# ETH_10M100M_RMII_LAN8742.net
KiCad netlist of a schematic drawn in Altium Designer
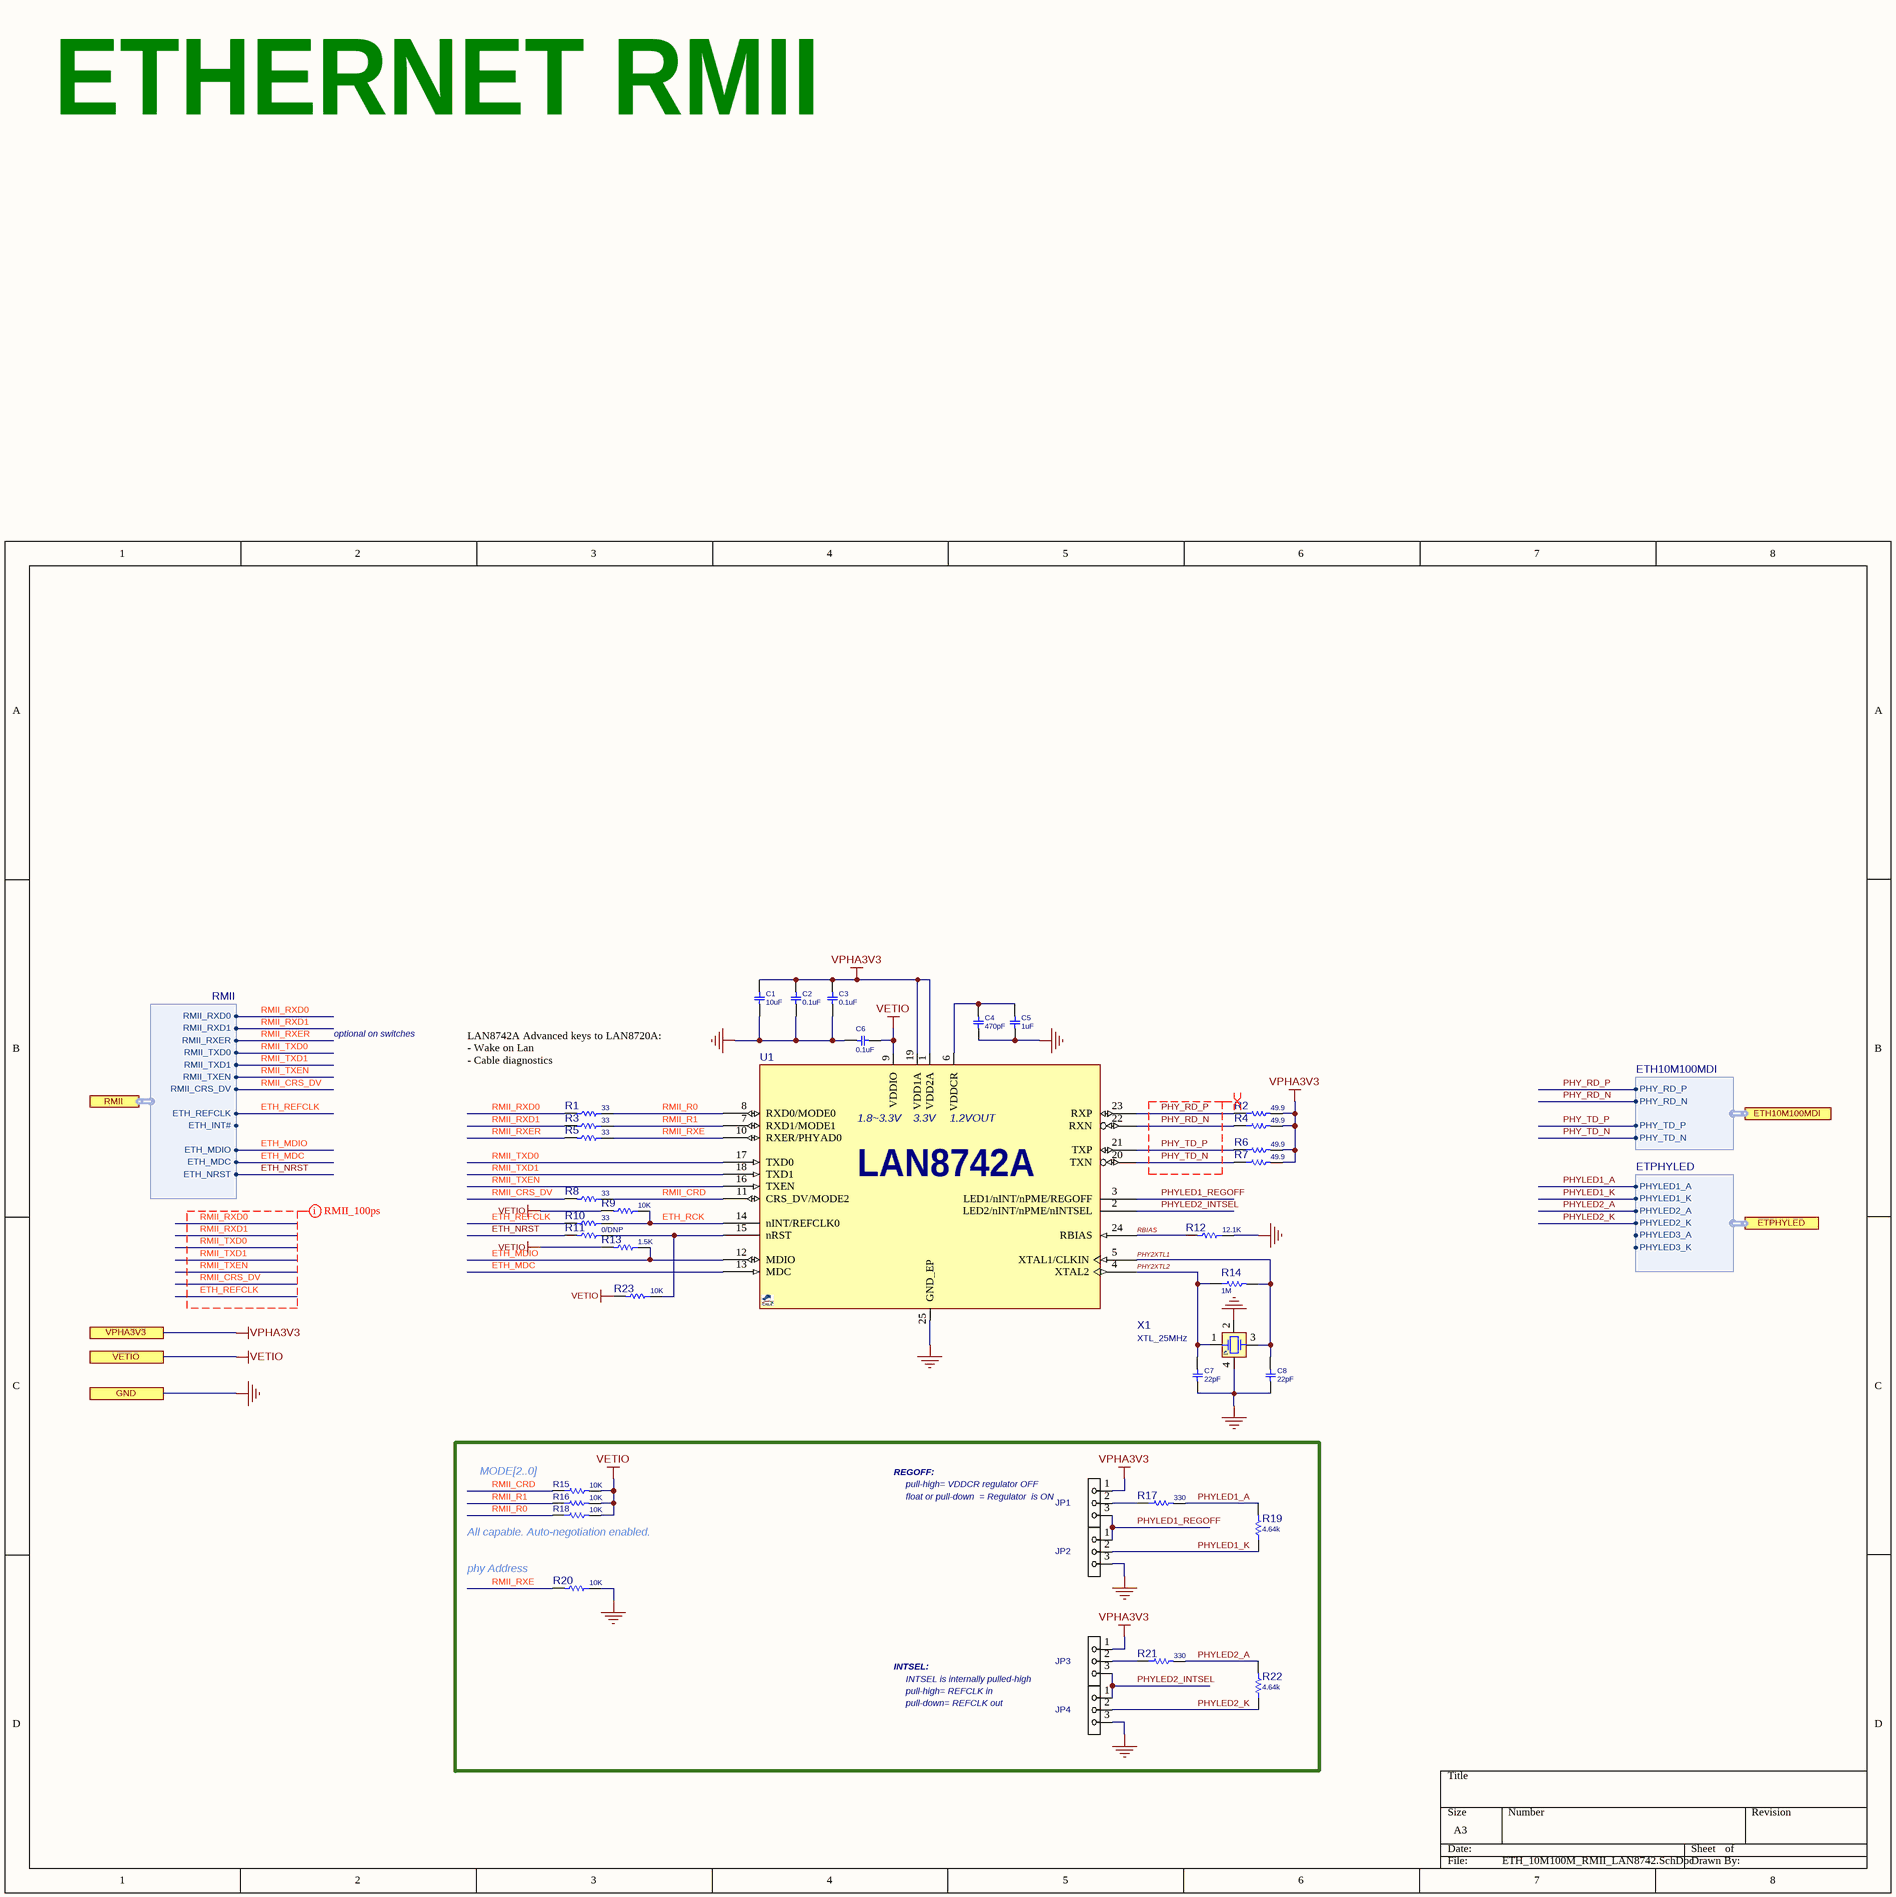
[diagram p0: ETH_10M100M_RMII_LAN8742.SchDoc]

(export (version "E")
  (design (tool "Eeschema 10.0.6"))
  (components
    (comp (ref "C1")
      (value "10uF")
      (footprint "C0402")
      (description "CAP, MLCC")
      (libsource (lib "mlcc_smd_passive") (part "CAP_SMD_MLCC_100n50TDK"))
    )
    (comp (ref "C2")
      (value "0.1uF")
      (footprint "C0402")
      (description "CAP, MLCC")
      (libsource (lib "mlcc_smd_passive") (part "CAP_SMD_MLCC_100n50TDK"))
    )
    (comp (ref "C3")
      (value "0.1uF")
      (footprint "C0402")
      (description "CAP, MLCC")
      (libsource (lib "mlcc_smd_passive") (part "CAP_SMD_MLCC_100n50TDK"))
    )
    (comp (ref "C4")
      (value "470pF")
      (footprint "C0402")
      (description "CAP, MLCC")
      (libsource (lib "mlcc_smd_passive") (part "CAP_SMD_MLCC_100n50TDK"))
    )
    (comp (ref "C5")
      (value "1uF")
      (footprint "C0402")
      (description "CAP, MLCC")
      (libsource (lib "mlcc_smd_passive") (part "CAP_SMD_MLCC_100n50TDK"))
    )
    (comp (ref "C6")
      (value "0.1uF")
      (footprint "C0402")
      (description "CAP, MLCC")
      (libsource (lib "mlcc_smd_passive") (part "CAP_SMD_MLCC_100n50TDK"))
    )
    (comp (ref "C7")
      (value "22pF")
      (footprint "C0402")
      (description "CAP, MLCC")
      (libsource (lib "mlcc_smd_passive") (part "CAP_SMD_MLCC_100n50TDK"))
    )
    (comp (ref "C8")
      (value "22pF")
      (footprint "C0402")
      (description "CAP, MLCC")
      (libsource (lib "mlcc_smd_passive") (part "CAP_SMD_MLCC_100n50TDK"))
    )
    (comp (ref "JP1")
      (value "JMPHDR3PIN")
      (footprint "JP_3_60W")
      (description "JUMPER, HEADER 3PIN")
      (fields (field (name "MANF") "MANF") (field (name "MANF_P#") "MANF_P#"))
      (libsource (lib "test-tp_jumper") (part "JUMPER_SOLDER_3P"))
    )
    (comp (ref "JP2")
      (value "JMPHDR3PIN")
      (footprint "JP_3_60W")
      (description "JUMPER, HEADER 3PIN")
      (fields (field (name "MANF") "MANF") (field (name "MANF_P#") "MANF_P#"))
      (libsource (lib "test-tp_jumper") (part "JUMPER_SOLDER_3P"))
    )
    (comp (ref "JP3")
      (value "JMPHDR3PIN")
      (footprint "JP_3_60W")
      (description "JUMPER, HEADER 3PIN")
      (fields (field (name "MANF") "MANF") (field (name "MANF_P#") "MANF_P#"))
      (libsource (lib "test-tp_jumper") (part "JUMPER_SOLDER_3P"))
    )
    (comp (ref "JP4")
      (value "JMPHDR3PIN")
      (footprint "JP_3_60W")
      (description "JUMPER, HEADER 3PIN")
      (fields (field (name "MANF") "MANF") (field (name "MANF_P#") "MANF_P#"))
      (libsource (lib "test-tp_jumper") (part "JUMPER_SOLDER_3P"))
    )
    (comp (ref "R1")
      (value "33")
      (footprint "R0402")
      (description "RESISTOR, SMD, THICK FILM, YAGEO")
      (fields (field (name "MANF_P#") "RC0402FR-071KL") (field (name "MANF") "Yageo"))
      (libsource (lib "res_smd_Yageo0402_thickfilm") (part "RES_SMD_1K_0402YK"))
    )
    (comp (ref "R2")
      (value "49.9")
      (footprint "R0402")
      (description "RESISTOR, SMD, THICK FILM, YAGEO")
      (fields (field (name "MANF_P#") "RC0402FR-071KL") (field (name "MANF") "Yageo"))
      (libsource (lib "res_smd_Yageo0402_thickfilm") (part "RES_SMD_1K_0402YK"))
    )
    (comp (ref "R3")
      (value "33")
      (footprint "R0402")
      (description "RESISTOR, SMD, THICK FILM, YAGEO")
      (fields (field (name "MANF_P#") "RC0402FR-071KL") (field (name "MANF") "Yageo"))
      (libsource (lib "res_smd_Yageo0402_thickfilm") (part "RES_SMD_1K_0402YK"))
    )
    (comp (ref "R4")
      (value "49.9")
      (footprint "R0402")
      (description "RESISTOR, SMD, THICK FILM, YAGEO")
      (fields (field (name "MANF_P#") "RC0402FR-071KL") (field (name "MANF") "Yageo"))
      (libsource (lib "res_smd_Yageo0402_thickfilm") (part "RES_SMD_1K_0402YK"))
    )
    (comp (ref "R5")
      (value "33")
      (footprint "R0402")
      (description "RESISTOR, SMD, THICK FILM, YAGEO")
      (fields (field (name "MANF_P#") "RC0402FR-071KL") (field (name "MANF") "Yageo"))
      (libsource (lib "res_smd_Yageo0402_thickfilm") (part "RES_SMD_1K_0402YK"))
    )
    (comp (ref "R6")
      (value "49.9")
      (footprint "R0402")
      (description "RESISTOR, SMD, THICK FILM, YAGEO")
      (fields (field (name "MANF_P#") "RC0402FR-071KL") (field (name "MANF") "Yageo"))
      (libsource (lib "res_smd_Yageo0402_thickfilm") (part "RES_SMD_1K_0402YK"))
    )
    (comp (ref "R7")
      (value "49.9")
      (footprint "R0402")
      (description "RESISTOR, SMD, THICK FILM, YAGEO")
      (fields (field (name "MANF_P#") "RC0402FR-071KL") (field (name "MANF") "Yageo"))
      (libsource (lib "res_smd_Yageo0402_thickfilm") (part "RES_SMD_1K_0402YK"))
    )
    (comp (ref "R8")
      (value "33")
      (footprint "R0402")
      (description "RESISTOR, SMD, THICK FILM, YAGEO")
      (fields (field (name "MANF_P#") "RC0402FR-071KL") (field (name "MANF") "Yageo"))
      (libsource (lib "res_smd_Yageo0402_thickfilm") (part "RES_SMD_1K_0402YK"))
    )
    (comp (ref "R9")
      (value "10K")
      (footprint "R0402")
      (description "RESISTOR, SMD, THICK FILM, YAGEO")
      (fields (field (name "MANF_P#") "RC0402FR-071KL") (field (name "MANF") "Yageo"))
      (libsource (lib "res_smd_Yageo0402_thickfilm") (part "RES_SMD_1K_0402YK"))
    )
    (comp (ref "R10")
      (value "33")
      (footprint "R0402")
      (description "RESISTOR, SMD, THICK FILM, YAGEO")
      (fields (field (name "MANF_P#") "RC0402FR-071KL") (field (name "MANF") "Yageo"))
      (libsource (lib "res_smd_Yageo0402_thickfilm") (part "RES_SMD_1K_0402YK"))
    )
    (comp (ref "R11")
      (value "0/DNP")
      (footprint "R0402")
      (description "RESISTOR, SMD, THICK FILM, YAGEO")
      (fields (field (name "MANF_P#") "RC0402FR-071KL") (field (name "MANF") "Yageo"))
      (libsource (lib "res_smd_Yageo0402_thickfilm") (part "RES_SMD_1K_0402YK"))
    )
    (comp (ref "R12")
      (value "12.1K")
      (footprint "R0402")
      (description "RESISTOR, SMD, THICK FILM, YAGEO")
      (fields (field (name "MANF_P#") "RC0402FR-071KL") (field (name "MANF") "Yageo"))
      (libsource (lib "res_smd_Yageo0402_thickfilm") (part "RES_SMD_1K_0402YK"))
    )
    (comp (ref "R13")
      (value "1.5K")
      (footprint "R0402")
      (description "RESISTOR, SMD, THICK FILM, YAGEO")
      (fields (field (name "MANF_P#") "RC0402FR-071KL") (field (name "MANF") "Yageo"))
      (libsource (lib "res_smd_Yageo0402_thickfilm") (part "RES_SMD_1K_0402YK"))
    )
    (comp (ref "R14")
      (value "1M")
      (footprint "R0402")
      (description "RESISTOR, SMD")
      (fields (field (name "MANF") "Yageo") (field (name "MANF_P#") "RC0402FR-071ML"))
      (libsource (lib "res_smd_KoaSpeer0402") (part "RES_SMD_10K_0402"))
    )
    (comp (ref "R15")
      (value "10K")
      (footprint "R0402")
      (description "RESISTOR, SMD, THICK FILM, YAGEO")
      (fields (field (name "MANF_P#") "RC0402FR-071KL") (field (name "MANF") "Yageo"))
      (libsource (lib "res_smd_Yageo0402_thickfilm") (part "RES_SMD_1K_0402YK"))
    )
    (comp (ref "R16")
      (value "10K")
      (footprint "R0402")
      (description "RESISTOR, SMD, THICK FILM, YAGEO")
      (fields (field (name "MANF_P#") "RC0402FR-071KL") (field (name "MANF") "Yageo"))
      (libsource (lib "res_smd_Yageo0402_thickfilm") (part "RES_SMD_1K_0402YK"))
    )
    (comp (ref "R17")
      (value "330")
      (footprint "R0402")
      (description "RESISTOR, SMD, THICK FILM, YAGEO")
      (fields (field (name "MANF_P#") "RC0402FR-071KL") (field (name "MANF") "Yageo"))
      (libsource (lib "res_smd_Yageo0402_thickfilm") (part "RES_SMD_1K_0402YK"))
    )
    (comp (ref "R18")
      (value "10K")
      (footprint "R0402")
      (description "RESISTOR, SMD, THICK FILM, YAGEO")
      (fields (field (name "MANF_P#") "RC0402FR-071KL") (field (name "MANF") "Yageo"))
      (libsource (lib "res_smd_Yageo0402_thickfilm") (part "RES_SMD_1K_0402YK"))
    )
    (comp (ref "R19")
      (value "4.64k")
      (footprint "R0402")
      (description "RESISTOR, SMD, THICK FILM, YAGEO")
      (fields (field (name "MANF_P#") "RC0402FR-071KL") (field (name "MANF") "Yageo"))
      (libsource (lib "res_smd_Yageo0402_thickfilm") (part "RES_SMD_1K_0402YK"))
    )
    (comp (ref "R20")
      (value "10K")
      (footprint "R0402")
      (description "RESISTOR, SMD, THICK FILM, YAGEO")
      (fields (field (name "MANF_P#") "RC0402FR-071KL") (field (name "MANF") "Yageo"))
      (libsource (lib "res_smd_Yageo0402_thickfilm") (part "RES_SMD_1K_0402YK"))
    )
    (comp (ref "R21")
      (value "330")
      (footprint "R0402")
      (description "RESISTOR, SMD, THICK FILM, YAGEO")
      (fields (field (name "MANF_P#") "RC0402FR-071KL") (field (name "MANF") "Yageo"))
      (libsource (lib "res_smd_Yageo0402_thickfilm") (part "RES_SMD_1K_0402YK"))
    )
    (comp (ref "R22")
      (value "4.64k")
      (footprint "R0402")
      (description "RESISTOR, SMD, THICK FILM, YAGEO")
      (fields (field (name "MANF_P#") "RC0402FR-071KL") (field (name "MANF") "Yageo"))
      (libsource (lib "res_smd_Yageo0402_thickfilm") (part "RES_SMD_1K_0402YK"))
    )
    (comp (ref "R23")
      (value "10K")
      (footprint "R0402")
      (description "RESISTOR, SMD, THICK FILM, YAGEO")
      (fields (field (name "MANF_P#") "RC0402FR-071KL") (field (name "MANF") "Yageo"))
      (libsource (lib "res_smd_Yageo0402_thickfilm") (part "RES_SMD_1K_0402YK"))
    )
    (comp (ref "U1")
      (value "LAN8742A")
      (footprint "QFN50_24T")
      (description "Ethernet Transceiver, 10/100, RMII, 1.6-3.6V QFN24")
      (fields (field (name "MANF") "SMSC, MICROCHIP") (field (name "MANF_P#") "LAN8742AI-CZ"))
      (libsource (lib "ethernet") (part "LAN8742_QFN24"))
    )
    (comp (ref "X1")
      (value "XTL_25MHz")
      (footprint "XTL_4_3225")
      (description "CRYSTAL 25.00 MHZ 18pF, 10PPM")
      (fields (field (name "MANF") "EPSON") (field (name "MANF_P#") "TSX-3225 25.0000MF10P-C3"))
      (libsource (lib "crystal_osc") (part "XTL_4_25MHz_3225"))
    )
  )
  (nets
    (net (code "4") (name "/ETH_MDC") (class "Default")
      (node (ref "U1") (pin "13") (pinfunction "MDC_13") (pintype "input"))
    )
    (net (code "5") (name "/ETH_MDIO") (class "Default")
      (node (ref "R13") (pin "1") (pinfunction "1_1") (pintype "passive"))
      (node (ref "U1") (pin "12") (pinfunction "MDIO_12") (pintype "bidirectional"))
    )
    (net (code "6") (name "/ETH_NRST") (class "Default")
      (node (ref "R11") (pin "2") (pinfunction "2_2") (pintype "passive"))
    )
    (net (code "7") (name "/ETH_RCK") (class "Default")
      (node (ref "R10") (pin "1") (pinfunction "1_1") (pintype "passive"))
      (node (ref "R9") (pin "1") (pinfunction "1_1") (pintype "passive"))
      (node (ref "U1") (pin "14") (pinfunction "nINT/REFCLK0_14") (pintype "passive"))
    )
    (net (code "8") (name "/ETH_REFCLK") (class "Default")
      (node (ref "R10") (pin "2") (pinfunction "2_2") (pintype "passive"))
    )
    (net (code "9") (name "/PHY2XTL1") (class "Default")
      (node (ref "C8") (pin "1") (pinfunction "1_1") (pintype "passive"))
      (node (ref "R14") (pin "2") (pinfunction "2_2") (pintype "passive"))
      (node (ref "U1") (pin "5") (pinfunction "XTAL1/CLKIN_5") (pintype "input"))
      (node (ref "X1") (pin "3") (pinfunction "XB_3") (pintype "passive"))
    )
    (net (code "10") (name "/PHY2XTL2") (class "Default")
      (node (ref "C7") (pin "1") (pinfunction "1_1") (pintype "passive"))
      (node (ref "R14") (pin "1") (pinfunction "1_1") (pintype "passive"))
      (node (ref "U1") (pin "4") (pinfunction "XTAL2_4") (pintype "output"))
      (node (ref "X1") (pin "1") (pinfunction "XA_1") (pintype "passive"))
    )
    (net (code "11") (name "/PHYLED1_A") (class "Default")
      (node (ref "R17") (pin "2") (pinfunction "2_2") (pintype "passive"))
      (node (ref "R19") (pin "2") (pinfunction "2_2") (pintype "passive"))
    )
    (net (code "12") (name "/PHYLED1_K") (class "Default")
      (node (ref "JP2") (pin "2") (pinfunction "2_2") (pintype "passive"))
      (node (ref "R19") (pin "1") (pinfunction "1_1") (pintype "passive"))
    )
    (net (code "13") (name "/PHYLED1_REGOFF") (class "Default")
      (node (ref "JP1") (pin "3") (pinfunction "3_3") (pintype "passive"))
      (node (ref "JP2") (pin "1") (pinfunction "1_1") (pintype "passive"))
      (node (ref "U1") (pin "3") (pinfunction "LED1/nINT/nPME/REGOFF_3") (pintype "passive"))
    )
    (net (code "14") (name "/PHYLED2_A") (class "Default")
      (node (ref "R21") (pin "2") (pinfunction "2_2") (pintype "passive"))
      (node (ref "R22") (pin "2") (pinfunction "2_2") (pintype "passive"))
    )
    (net (code "15") (name "/PHYLED2_INTSEL") (class "Default")
      (node (ref "JP3") (pin "3") (pinfunction "3_3") (pintype "passive"))
      (node (ref "JP4") (pin "1") (pinfunction "1_1") (pintype "passive"))
      (node (ref "U1") (pin "2") (pinfunction "LED2/nINT/nPME/nINTSEL_2") (pintype "passive"))
    )
    (net (code "16") (name "/PHYLED2_K") (class "Default")
      (node (ref "JP4") (pin "2") (pinfunction "2_2") (pintype "passive"))
      (node (ref "R22") (pin "1") (pinfunction "1_1") (pintype "passive"))
    )
    (net (code "17") (name "/PHY_RD_N") (class "Default")
      (node (ref "R4") (pin "1") (pinfunction "1_1") (pintype "passive"))
      (node (ref "U1") (pin "22") (pinfunction "RXN_22") (pintype "bidirectional"))
    )
    (net (code "18") (name "/PHY_RD_P") (class "Default")
      (node (ref "R2") (pin "1") (pinfunction "1_1") (pintype "passive"))
      (node (ref "U1") (pin "23") (pinfunction "RXP_23") (pintype "bidirectional"))
    )
    (net (code "19") (name "/PHY_TD_N") (class "Default")
      (node (ref "R7") (pin "1") (pinfunction "1_1") (pintype "passive"))
      (node (ref "U1") (pin "20") (pinfunction "TXN_20") (pintype "bidirectional"))
    )
    (net (code "20") (name "/PHY_TD_P") (class "Default")
      (node (ref "R6") (pin "1") (pinfunction "1_1") (pintype "passive"))
      (node (ref "U1") (pin "21") (pinfunction "TXP_21") (pintype "bidirectional"))
    )
    (net (code "21") (name "/RBIAS") (class "Default")
      (node (ref "R12") (pin "2") (pinfunction "2_2") (pintype "passive"))
      (node (ref "U1") (pin "24") (pinfunction "RBIAS_24") (pintype "input"))
    )
    (net (code "22") (name "/RMII_CRD") (class "Default")
      (node (ref "R15") (pin "1") (pinfunction "1_1") (pintype "passive"))
      (node (ref "R8") (pin "1") (pinfunction "1_1") (pintype "passive"))
      (node (ref "U1") (pin "11") (pinfunction "CRS_DV/MODE2_11") (pintype "bidirectional"))
    )
    (net (code "23") (name "/RMII_CRS_DV") (class "Default")
      (node (ref "R8") (pin "2") (pinfunction "2_2") (pintype "passive"))
    )
    (net (code "24") (name "/RMII_R0") (class "Default")
      (node (ref "R1") (pin "1") (pinfunction "1_1") (pintype "passive"))
      (node (ref "R18") (pin "1") (pinfunction "1_1") (pintype "passive"))
      (node (ref "U1") (pin "8") (pinfunction "RXD0/MODE0_8") (pintype "bidirectional"))
    )
    (net (code "25") (name "/RMII_R1") (class "Default")
      (node (ref "R16") (pin "1") (pinfunction "1_1") (pintype "passive"))
      (node (ref "R3") (pin "1") (pinfunction "1_1") (pintype "passive"))
      (node (ref "U1") (pin "7") (pinfunction "RXD1/MODE1_7") (pintype "bidirectional"))
    )
    (net (code "26") (name "/RMII_RXD0") (class "Default")
      (node (ref "R1") (pin "2") (pinfunction "2_2") (pintype "passive"))
    )
    (net (code "27") (name "/RMII_RXD1") (class "Default")
      (node (ref "R3") (pin "2") (pinfunction "2_2") (pintype "passive"))
    )
    (net (code "28") (name "/RMII_RXE") (class "Default")
      (node (ref "R20") (pin "2") (pinfunction "2_2") (pintype "passive"))
      (node (ref "R5") (pin "1") (pinfunction "1_1") (pintype "passive"))
      (node (ref "U1") (pin "10") (pinfunction "RXER/PHYAD0_10") (pintype "bidirectional"))
    )
    (net (code "29") (name "/RMII_RXER") (class "Default")
      (node (ref "R5") (pin "2") (pinfunction "2_2") (pintype "passive"))
    )
    (net (code "30") (name "/RMII_TXD0") (class "Default")
      (node (ref "U1") (pin "17") (pinfunction "TXD0_17") (pintype "input"))
    )
    (net (code "31") (name "/RMII_TXD1") (class "Default")
      (node (ref "U1") (pin "18") (pinfunction "TXD1_18") (pintype "input"))
    )
    (net (code "32") (name "/RMII_TXEN") (class "Default")
      (node (ref "U1") (pin "16") (pinfunction "TXEN_16") (pintype "input"))
    )
    (net (code "36") (name "GND") (class "Default")
      (node (ref "C1") (pin "2") (pinfunction "2_2") (pintype "passive"))
      (node (ref "C2") (pin "2") (pinfunction "2_2") (pintype "passive"))
      (node (ref "C3") (pin "2") (pinfunction "2_2") (pintype "passive"))
      (node (ref "C4") (pin "2") (pinfunction "2_2") (pintype "passive"))
      (node (ref "C5") (pin "2") (pinfunction "2_2") (pintype "passive"))
      (node (ref "C6") (pin "2") (pinfunction "2_2") (pintype "passive"))
      (node (ref "C7") (pin "2") (pinfunction "2_2") (pintype "passive"))
      (node (ref "C8") (pin "2") (pinfunction "2_2") (pintype "passive"))
      (node (ref "JP2") (pin "3") (pinfunction "3_3") (pintype "passive"))
      (node (ref "JP4") (pin "3") (pinfunction "3_3") (pintype "passive"))
      (node (ref "R12") (pin "1") (pinfunction "1_1") (pintype "passive"))
      (node (ref "R20") (pin "1") (pinfunction "1_1") (pintype "passive"))
      (node (ref "U1") (pin "25") (pinfunction "GND_EP_25") (pintype "power_in"))
      (node (ref "X1") (pin "2") (pinfunction "GND1_2") (pintype "passive"))
      (node (ref "X1") (pin "4") (pinfunction "GND2_4") (pintype "passive"))
    )
    (net (code "37") (name "Net-(JP1-Pad2)") (class "Default")
      (node (ref "JP1") (pin "2") (pinfunction "2_2") (pintype "passive"))
      (node (ref "R17") (pin "1") (pinfunction "1_1") (pintype "passive"))
    )
    (net (code "38") (name "Net-(JP3-Pad2)") (class "Default")
      (node (ref "JP3") (pin "2") (pinfunction "2_2") (pintype "passive"))
      (node (ref "R21") (pin "1") (pinfunction "1_1") (pintype "passive"))
    )
    (net (code "39") (name "Net-(U1-VDDCR)") (class "Default")
      (node (ref "C4") (pin "1") (pinfunction "1_1") (pintype "passive"))
      (node (ref "C5") (pin "1") (pinfunction "1_1") (pintype "passive"))
      (node (ref "U1") (pin "6") (pinfunction "VDDCR_6") (pintype "power_in"))
    )
    (net (code "40") (name "Net-(U1-nRST)") (class "Default")
      (node (ref "R11") (pin "1") (pinfunction "1_1") (pintype "passive"))
      (node (ref "R23") (pin "1") (pinfunction "1_1") (pintype "passive"))
      (node (ref "U1") (pin "15") (pinfunction "nRST_15") (pintype "passive"))
    )
    (net (code "41") (name "VETIO") (class "Default")
      (node (ref "C6") (pin "1") (pinfunction "1_1") (pintype "passive"))
      (node (ref "R13") (pin "2") (pinfunction "2_2") (pintype "passive"))
      (node (ref "R15") (pin "2") (pinfunction "2_2") (pintype "passive"))
      (node (ref "R16") (pin "2") (pinfunction "2_2") (pintype "passive"))
      (node (ref "R18") (pin "2") (pinfunction "2_2") (pintype "passive"))
      (node (ref "R23") (pin "2") (pinfunction "2_2") (pintype "passive"))
      (node (ref "R9") (pin "2") (pinfunction "2_2") (pintype "passive"))
      (node (ref "U1") (pin "9") (pinfunction "VDDIO_9") (pintype "power_in"))
    )
    (net (code "42") (name "VPHA3V3") (class "Default")
      (node (ref "C1") (pin "1") (pinfunction "1_1") (pintype "passive"))
      (node (ref "C2") (pin "1") (pinfunction "1_1") (pintype "passive"))
      (node (ref "C3") (pin "1") (pinfunction "1_1") (pintype "passive"))
      (node (ref "JP1") (pin "1") (pinfunction "1_1") (pintype "passive"))
      (node (ref "JP3") (pin "1") (pinfunction "1_1") (pintype "passive"))
      (node (ref "R2") (pin "2") (pinfunction "2_2") (pintype "passive"))
      (node (ref "R4") (pin "2") (pinfunction "2_2") (pintype "passive"))
      (node (ref "R6") (pin "2") (pinfunction "2_2") (pintype "passive"))
      (node (ref "R7") (pin "2") (pinfunction "2_2") (pintype "passive"))
      (node (ref "U1") (pin "1") (pinfunction "VDD2A_1") (pintype "power_in"))
      (node (ref "U1") (pin "19") (pinfunction "VDD1A_19") (pintype "power_in"))
    )
  )
)
